# PAGE_06-Copper_Ports.net
KiCad netlist of a schematic drawn in Altium Designer
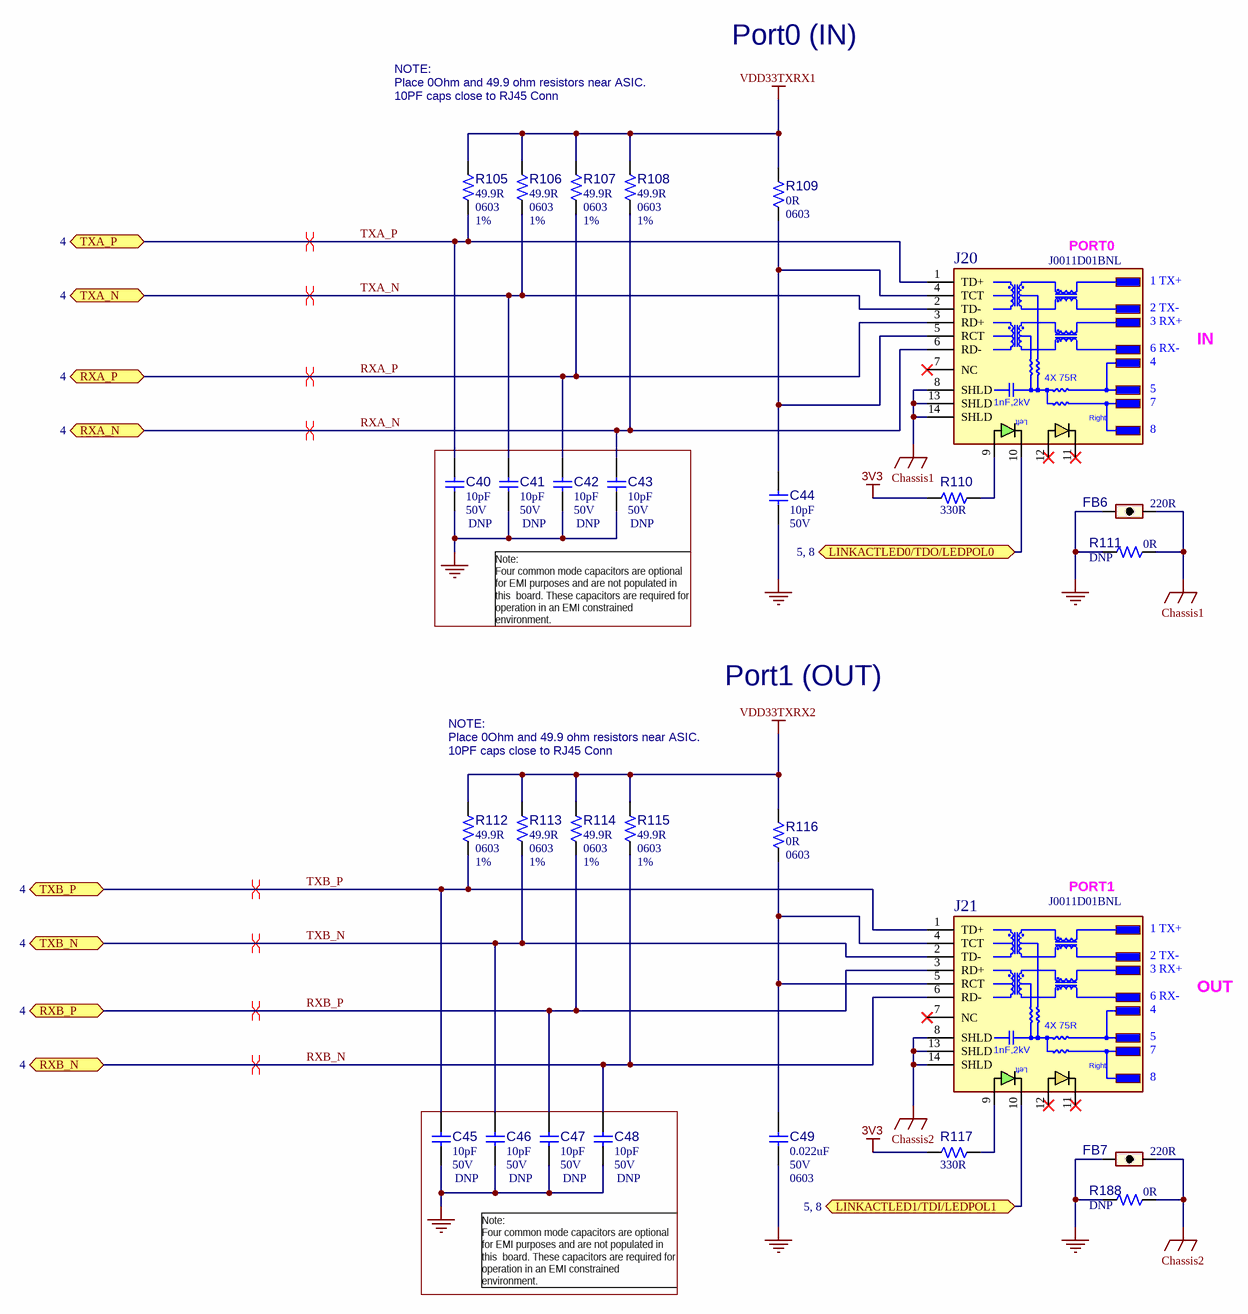
[diagram p0: PAGE 06-Copper Ports.SchDoc]

(export (version "E")
  (design (tool "Eeschema 10.0.6"))
  (components
    (comp (ref "C40")
      (value "10pF")
      (footprint "CAP_C_0603")
      (description "Capacitor")
      (fields
        (field (name "VOLTAGE") "50V")
        (field (name "TOLERANCE") "5%")
        (field (name "POPULATED") "DNP")
        (field (name "Comment") "Capacitor NP")
      )
      (libsource (lib "MCHP-CDB") (part "Capacitor NP"))
    )
    (comp (ref "C41")
      (value "10pF")
      (footprint "CAP_C_0603")
      (description "Capacitor")
      (fields
        (field (name "VOLTAGE") "50V")
        (field (name "TOLERANCE") "5%")
        (field (name "POPULATED") "DNP")
        (field (name "Comment") "Capacitor NP")
      )
      (libsource (lib "MCHP-CDB") (part "Capacitor NP"))
    )
    (comp (ref "C42")
      (value "10pF")
      (footprint "CAP_C_0603")
      (description "Capacitor")
      (fields
        (field (name "VOLTAGE") "50V")
        (field (name "TOLERANCE") "5%")
        (field (name "POPULATED") "DNP")
        (field (name "Comment") "Capacitor NP")
      )
      (libsource (lib "MCHP-CDB") (part "Capacitor NP"))
    )
    (comp (ref "C43")
      (value "10pF")
      (footprint "CAP_C_0603")
      (description "Capacitor")
      (fields
        (field (name "VOLTAGE") "50V")
        (field (name "TOLERANCE") "5%")
        (field (name "POPULATED") "DNP")
        (field (name "Comment") "Capacitor NP")
      )
      (libsource (lib "MCHP-CDB") (part "Capacitor NP"))
    )
    (comp (ref "C44")
      (value "10pF")
      (footprint "CAP_C_0603")
      (description "Capacitor")
      (fields
        (field (name "VOLTAGE") "50V")
        (field (name "TOLERANCE") "5%")
        (field (name "Comment") "Capacitor NP")
      )
      (libsource (lib "MCHP-CDB") (part "Capacitor NP"))
    )
    (comp (ref "C45")
      (value "10pF")
      (footprint "CAP_C_0603")
      (description "Capacitor")
      (fields
        (field (name "VOLTAGE") "50V")
        (field (name "TOLERANCE") "5%")
        (field (name "POPULATED") "DNP")
        (field (name "Comment") "Capacitor NP")
      )
      (libsource (lib "MCHP-CDB") (part "Capacitor NP"))
    )
    (comp (ref "C46")
      (value "10pF")
      (footprint "CAP_C_0603")
      (description "Capacitor")
      (fields
        (field (name "VOLTAGE") "50V")
        (field (name "TOLERANCE") "5%")
        (field (name "POPULATED") "DNP")
        (field (name "Comment") "Capacitor NP")
      )
      (libsource (lib "MCHP-CDB") (part "Capacitor NP"))
    )
    (comp (ref "C47")
      (value "10pF")
      (footprint "CAP_C_0603")
      (description "Capacitor")
      (fields
        (field (name "VOLTAGE") "50V")
        (field (name "TOLERANCE") "5%")
        (field (name "POPULATED") "DNP")
        (field (name "Comment") "Capacitor NP")
      )
      (libsource (lib "MCHP-CDB") (part "Capacitor NP"))
    )
    (comp (ref "C48")
      (value "10pF")
      (footprint "CAP_C_0603")
      (description "Capacitor")
      (fields
        (field (name "VOLTAGE") "50V")
        (field (name "TOLERANCE") "5%")
        (field (name "POPULATED") "DNP")
        (field (name "Comment") "Capacitor NP")
      )
      (libsource (lib "MCHP-CDB") (part "Capacitor NP"))
    )
    (comp (ref "C49")
      (value "0.022uF")
      (footprint "CAP_C_0603")
      (description "Capacitor")
      (fields
        (field (name "VOLTAGE") "50V")
        (field (name "PACKAGE") "0603")
        (field (name "TOLERANCE") "5%")
        (field (name "Comment") "Capacitor NP")
      )
      (libsource (lib "MCHP-CDB") (part "Capacitor NP"))
    )
    (comp (ref "FB6")
      (value "220R")
      (footprint "IND_C_0603")
      (fields (field (name "Comment") "Ferrite Bead") (field (name "OWNER") "Sompoch Loboonlert"))
      (libsource (lib "MCHP-CDB-Offline") (part "Ferrite Bead"))
    )
    (comp (ref "FB7")
      (value "220R")
      (footprint "IND_C_0603")
      (fields (field (name "Comment") "Ferrite Bead") (field (name "OWNER") "Sompoch Loboonlert"))
      (libsource (lib "MCHP-CDB-Offline") (part "Ferrite Bead"))
    )
    (comp (ref "J20")
      (value "J0011D01BNL")
      (footprint "J00-0045NL_RJ45_connector")
      (fields (field (name "Comment") "RJ45 J00-0045NL") (field (name "OWNER") "Sam Charles"))
      (libsource (lib "MCHP-CDB") (part "RJ45 J00-0045NL"))
    )
    (comp (ref "J21")
      (value "J0011D01BNL")
      (footprint "J00-0045NL_RJ45_connector")
      (fields (field (name "Comment") "RJ45 J00-0045NL") (field (name "OWNER") "Sam Charles"))
      (libsource (lib "MCHP-CDB") (part "RJ45 J00-0045NL"))
    )
    (comp (ref "R105")
      (value "49.9R")
      (footprint "RES_C_0603")
      (description "Resistor")
      (fields
        (field (name "PACKAGE") "0603")
        (field (name "TOLERANCE") "1%")
        (field (name "VOLTAGE") "75V")
        (field (name "POWER") "1/10W")
        (field (name "OWNER") "Adrian T (M91397)")
      )
      (libsource (lib "MCHP-CDB-Offline") (part "Resistor"))
    )
    (comp (ref "R106")
      (value "49.9R")
      (footprint "RES_C_0603")
      (description "Resistor")
      (fields
        (field (name "PACKAGE") "0603")
        (field (name "TOLERANCE") "1%")
        (field (name "VOLTAGE") "75V")
        (field (name "POWER") "1/10W")
        (field (name "OWNER") "Adrian T (M91397)")
      )
      (libsource (lib "MCHP-CDB-Offline") (part "Resistor"))
    )
    (comp (ref "R107")
      (value "49.9R")
      (footprint "RES_C_0603")
      (description "Resistor")
      (fields
        (field (name "PACKAGE") "0603")
        (field (name "TOLERANCE") "1%")
        (field (name "VOLTAGE") "75V")
        (field (name "POWER") "1/10W")
        (field (name "OWNER") "Adrian T (M91397)")
      )
      (libsource (lib "MCHP-CDB-Offline") (part "Resistor"))
    )
    (comp (ref "R108")
      (value "49.9R")
      (footprint "RES_C_0603")
      (description "Resistor")
      (fields
        (field (name "PACKAGE") "0603")
        (field (name "TOLERANCE") "1%")
        (field (name "VOLTAGE") "75V")
        (field (name "POWER") "1/10W")
        (field (name "OWNER") "Adrian T (M91397)")
      )
      (libsource (lib "MCHP-CDB-Offline") (part "Resistor"))
    )
    (comp (ref "R109")
      (value "0R")
      (footprint "RES_C_0603")
      (description "Resistor")
      (fields (field (name "PACKAGE") "0603") (field (name "POWER") "1/10W"))
      (libsource (lib "MCHP-CDB-Offline") (part "Resistor"))
    )
    (comp (ref "R110")
      (value "330R")
      (footprint "RES_C_0603")
      (description "Resistor")
      (fields (field (name "TOLERANCE") "5%") (field (name "VOLTAGE") "50V"))
      (libsource (lib "MCHP-CDB") (part "Resistor"))
    )
    (comp (ref "R111")
      (value "0R")
      (footprint "RES_C_0603")
      (description "Resistor")
      (fields
        (field (name "POWER") "1/10W")
        (field (name "POPULATED") "DNP")
        (field (name "OWNER") "Steve Dziaba")
      )
      (libsource (lib "MCHP-CDB") (part "Resistor"))
    )
    (comp (ref "R112")
      (value "49.9R")
      (footprint "RES_C_0603")
      (description "Resistor")
      (fields
        (field (name "PACKAGE") "0603")
        (field (name "TOLERANCE") "1%")
        (field (name "VOLTAGE") "75V")
        (field (name "POWER") "1/10W")
        (field (name "OWNER") "Adrian T (M91397)")
      )
      (libsource (lib "MCHP-CDB-Offline") (part "Resistor"))
    )
    (comp (ref "R113")
      (value "49.9R")
      (footprint "RES_C_0603")
      (description "Resistor")
      (fields
        (field (name "PACKAGE") "0603")
        (field (name "TOLERANCE") "1%")
        (field (name "VOLTAGE") "75V")
        (field (name "POWER") "1/10W")
        (field (name "OWNER") "Adrian T (M91397)")
      )
      (libsource (lib "MCHP-CDB-Offline") (part "Resistor"))
    )
    (comp (ref "R114")
      (value "49.9R")
      (footprint "RES_C_0603")
      (description "Resistor")
      (fields
        (field (name "PACKAGE") "0603")
        (field (name "TOLERANCE") "1%")
        (field (name "VOLTAGE") "75V")
        (field (name "POWER") "1/10W")
        (field (name "OWNER") "Adrian T (M91397)")
      )
      (libsource (lib "MCHP-CDB-Offline") (part "Resistor"))
    )
    (comp (ref "R115")
      (value "49.9R")
      (footprint "RES_C_0603")
      (description "Resistor")
      (fields
        (field (name "PACKAGE") "0603")
        (field (name "TOLERANCE") "1%")
        (field (name "VOLTAGE") "75V")
        (field (name "POWER") "1/10W")
        (field (name "OWNER") "Adrian T (M91397)")
      )
      (libsource (lib "MCHP-CDB-Offline") (part "Resistor"))
    )
    (comp (ref "R116")
      (value "0R")
      (footprint "RES_C_0603")
      (description "Resistor")
      (fields (field (name "PACKAGE") "0603") (field (name "POWER") "1/10W"))
      (libsource (lib "MCHP-CDB-Offline") (part "Resistor"))
    )
    (comp (ref "R117")
      (value "330R")
      (footprint "RES_C_0603")
      (description "Resistor")
      (fields (field (name "TOLERANCE") "5%") (field (name "VOLTAGE") "50V"))
      (libsource (lib "MCHP-CDB") (part "Resistor"))
    )
    (comp (ref "R188")
      (value "0R")
      (footprint "RES_C_0603")
      (description "Resistor")
      (fields
        (field (name "POWER") "1/10W")
        (field (name "POPULATED") "DNP")
        (field (name "OWNER") "Steve Dziaba")
      )
      (libsource (lib "MCHP-CDB") (part "Resistor"))
    )
  )
  (nets
    (net (code "1") (name "/LINKACTLED0{slash}TDO{slash}LEDPOL0") (class "Default")
      (node (ref "J20") (pin "10") (pinfunction "Cy_10") (pintype "passive"))
    )
    (net (code "2") (name "/LINKACTLED1{slash}TDI{slash}LEDPOL1") (class "Default")
      (node (ref "J21") (pin "10") (pinfunction "Cy_10") (pintype "passive"))
    )
    (net (code "3") (name "/RXA_N") (class "Default")
      (node (ref "C43") (pin "2") (pinfunction "2_2") (pintype "passive"))
      (node (ref "J20") (pin "6") (pinfunction "RD-_6") (pintype "passive"))
      (node (ref "R108") (pin "1") (pinfunction "1_1") (pintype "passive"))
    )
    (net (code "4") (name "/RXA_P") (class "Default")
      (node (ref "C42") (pin "2") (pinfunction "2_2") (pintype "passive"))
      (node (ref "J20") (pin "3") (pinfunction "RD+_3") (pintype "passive"))
      (node (ref "R107") (pin "1") (pinfunction "1_1") (pintype "passive"))
    )
    (net (code "5") (name "/RXB_N") (class "Default")
      (node (ref "C48") (pin "2") (pinfunction "2_2") (pintype "passive"))
      (node (ref "J21") (pin "6") (pinfunction "RD-_6") (pintype "passive"))
      (node (ref "R115") (pin "1") (pinfunction "1_1") (pintype "passive"))
    )
    (net (code "6") (name "/RXB_P") (class "Default")
      (node (ref "C47") (pin "2") (pinfunction "2_2") (pintype "passive"))
      (node (ref "J21") (pin "3") (pinfunction "RD+_3") (pintype "passive"))
      (node (ref "R114") (pin "1") (pinfunction "1_1") (pintype "passive"))
    )
    (net (code "7") (name "/TXA_N") (class "Default")
      (node (ref "C41") (pin "2") (pinfunction "2_2") (pintype "passive"))
      (node (ref "J20") (pin "2") (pinfunction "TD-_2") (pintype "passive"))
      (node (ref "R106") (pin "1") (pinfunction "1_1") (pintype "passive"))
    )
    (net (code "8") (name "/TXA_P") (class "Default")
      (node (ref "C40") (pin "2") (pinfunction "2_2") (pintype "passive"))
      (node (ref "J20") (pin "1") (pinfunction "TD+_1") (pintype "passive"))
      (node (ref "R105") (pin "1") (pinfunction "1_1") (pintype "passive"))
    )
    (net (code "9") (name "/TXB_N") (class "Default")
      (node (ref "C46") (pin "2") (pinfunction "2_2") (pintype "passive"))
      (node (ref "J21") (pin "2") (pinfunction "TD-_2") (pintype "passive"))
      (node (ref "R113") (pin "1") (pinfunction "1_1") (pintype "passive"))
    )
    (net (code "10") (name "/TXB_P") (class "Default")
      (node (ref "C45") (pin "2") (pinfunction "2_2") (pintype "passive"))
      (node (ref "J21") (pin "1") (pinfunction "TD+_1") (pintype "passive"))
      (node (ref "R112") (pin "1") (pinfunction "1_1") (pintype "passive"))
    )
    (net (code "11") (name "3V3") (class "Default")
      (node (ref "R110") (pin "1") (pinfunction "1_1") (pintype "passive"))
      (node (ref "R117") (pin "1") (pinfunction "1_1") (pintype "passive"))
    )
    (net (code "12") (name "Chassis1") (class "Default")
      (node (ref "FB6") (pin "2") (pinfunction "2_2") (pintype "passive"))
      (node (ref "J20") (pin "13") (pinfunction "SHLD_13") (pintype "passive"))
      (node (ref "J20") (pin "14") (pinfunction "SHLD_14") (pintype "passive"))
      (node (ref "J20") (pin "8") (pinfunction "SHLD_8") (pintype "passive"))
      (node (ref "R111") (pin "2") (pinfunction "2_2") (pintype "passive"))
    )
    (net (code "13") (name "Chassis2") (class "Default")
      (node (ref "FB7") (pin "2") (pinfunction "2_2") (pintype "passive"))
      (node (ref "J21") (pin "13") (pinfunction "SHLD_13") (pintype "passive"))
      (node (ref "J21") (pin "14") (pinfunction "SHLD_14") (pintype "passive"))
      (node (ref "J21") (pin "8") (pinfunction "SHLD_8") (pintype "passive"))
      (node (ref "R188") (pin "2") (pinfunction "2_2") (pintype "passive"))
    )
    (net (code "14") (name "GND") (class "Default")
      (node (ref "C40") (pin "1") (pinfunction "1_1") (pintype "passive"))
      (node (ref "C41") (pin "1") (pinfunction "1_1") (pintype "passive"))
      (node (ref "C42") (pin "1") (pinfunction "1_1") (pintype "passive"))
      (node (ref "C43") (pin "1") (pinfunction "1_1") (pintype "passive"))
      (node (ref "C44") (pin "1") (pinfunction "1_1") (pintype "passive"))
      (node (ref "C45") (pin "1") (pinfunction "1_1") (pintype "passive"))
      (node (ref "C46") (pin "1") (pinfunction "1_1") (pintype "passive"))
      (node (ref "C47") (pin "1") (pinfunction "1_1") (pintype "passive"))
      (node (ref "C48") (pin "1") (pinfunction "1_1") (pintype "passive"))
      (node (ref "C49") (pin "1") (pinfunction "1_1") (pintype "passive"))
      (node (ref "FB6") (pin "1") (pinfunction "1_1") (pintype "passive"))
      (node (ref "FB7") (pin "1") (pinfunction "1_1") (pintype "passive"))
      (node (ref "R111") (pin "1") (pinfunction "1_1") (pintype "passive"))
      (node (ref "R188") (pin "1") (pinfunction "1_1") (pintype "passive"))
    )
    (net (code "15") (name "Net-(J20-Ay)") (class "Default")
      (node (ref "J20") (pin "9") (pinfunction "Ay_9") (pintype "passive"))
      (node (ref "R110") (pin "2") (pinfunction "2_2") (pintype "passive"))
    )
    (net (code "16") (name "Net-(J20-RCT)") (class "Default")
      (node (ref "C44") (pin "2") (pinfunction "2_2") (pintype "passive"))
      (node (ref "J20") (pin "4") (pinfunction "TCT_4") (pintype "passive"))
      (node (ref "J20") (pin "5") (pinfunction "RCT_5") (pintype "passive"))
      (node (ref "R109") (pin "1") (pinfunction "1_1") (pintype "passive"))
    )
    (net (code "17") (name "Net-(J21-Ay)") (class "Default")
      (node (ref "J21") (pin "9") (pinfunction "Ay_9") (pintype "passive"))
      (node (ref "R117") (pin "2") (pinfunction "2_2") (pintype "passive"))
    )
    (net (code "18") (name "Net-(J21-RCT)") (class "Default")
      (node (ref "C49") (pin "2") (pinfunction "2_2") (pintype "passive"))
      (node (ref "J21") (pin "4") (pinfunction "TCT_4") (pintype "passive"))
      (node (ref "J21") (pin "5") (pinfunction "RCT_5") (pintype "passive"))
      (node (ref "R116") (pin "1") (pinfunction "1_1") (pintype "passive"))
    )
    (net (code "19") (name "VDD33TXRX1") (class "Default")
      (node (ref "R105") (pin "2") (pinfunction "2_2") (pintype "passive"))
      (node (ref "R106") (pin "2") (pinfunction "2_2") (pintype "passive"))
      (node (ref "R107") (pin "2") (pinfunction "2_2") (pintype "passive"))
      (node (ref "R108") (pin "2") (pinfunction "2_2") (pintype "passive"))
      (node (ref "R109") (pin "2") (pinfunction "2_2") (pintype "passive"))
    )
    (net (code "20") (name "VDD33TXRX2") (class "Default")
      (node (ref "R112") (pin "2") (pinfunction "2_2") (pintype "passive"))
      (node (ref "R113") (pin "2") (pinfunction "2_2") (pintype "passive"))
      (node (ref "R114") (pin "2") (pinfunction "2_2") (pintype "passive"))
      (node (ref "R115") (pin "2") (pinfunction "2_2") (pintype "passive"))
      (node (ref "R116") (pin "2") (pinfunction "2_2") (pintype "passive"))
    )
    (net (code "21") (name "unconnected-(J20-Ag-Pad11)") (class "Default")
      (node (ref "J20") (pin "11") (pinfunction "Ag_11") (pintype "passive+no_connect"))
    )
    (net (code "22") (name "unconnected-(J20-Cg-Pad12)") (class "Default")
      (node (ref "J20") (pin "12") (pinfunction "Cg_12") (pintype "passive+no_connect"))
    )
    (net (code "23") (name "unconnected-(J20-NC-Pad7)") (class "Default")
      (node (ref "J20") (pin "7") (pinfunction "NC_7") (pintype "passive+no_connect"))
    )
    (net (code "24") (name "unconnected-(J21-Ag-Pad11)") (class "Default")
      (node (ref "J21") (pin "11") (pinfunction "Ag_11") (pintype "passive+no_connect"))
    )
    (net (code "25") (name "unconnected-(J21-Cg-Pad12)") (class "Default")
      (node (ref "J21") (pin "12") (pinfunction "Cg_12") (pintype "passive+no_connect"))
    )
    (net (code "26") (name "unconnected-(J21-NC-Pad7)") (class "Default")
      (node (ref "J21") (pin "7") (pinfunction "NC_7") (pintype "passive+no_connect"))
    )
  )
)
